# SIM_CARD.net
KiCad netlist of a schematic drawn in Altium Designer
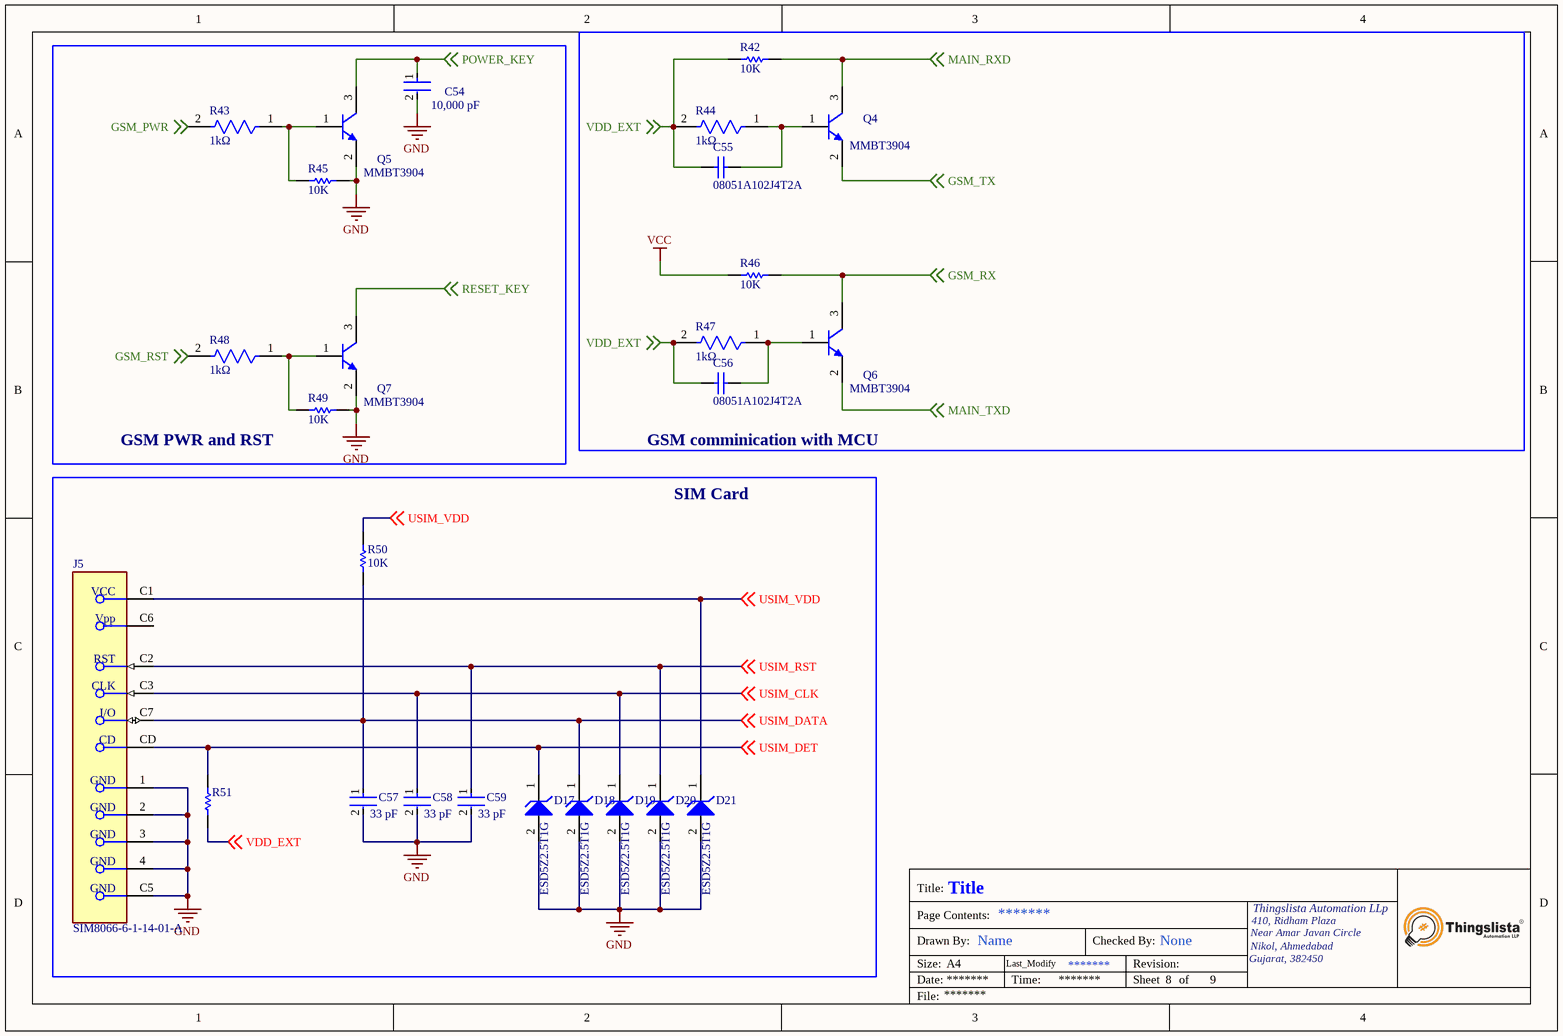
[diagram p0: SIM CARD.SchDoc]

(export (version "E")
  (design (tool "Eeschema 10.0.6"))
  (components
    (comp (ref "C54")
      (value "10,000 pF")
      (footprint "FP-C0805C-DN-MFG")
      (description "CAP CER 10000PF 200V X7R 0805")
      (fields
        (field (name "OCTOPART") "https://octopart.com/c0805c103k2ractu-kemet-9138347")
        (field (name "MANUFACTURER PART NUMBER") "C0805C103K2RACTU")
      )
      (libsource (lib "Altium Content Vault") (part "b4654b650e69147ec39a6b967a45e02"))
    )
    (comp (ref "C55")
      (value "08051A102J4T2A")
      (footprint "CAPC2013X94X50NL20T25")
      (fields (field (name "MANUFACTURER") "AVX Interconnect / Elco"))
      (libsource (lib "Altium Content Vault") (part "CAP"))
    )
    (comp (ref "C56")
      (value "08051A102J4T2A")
      (footprint "CAPC2013X94X50NL20T25")
      (fields (field (name "MANUFACTURER") "AVX Interconnect / Elco"))
      (libsource (lib "Altium Content Vault") (part "CAP"))
    )
    (comp (ref "C57")
      (value "33 pF")
      (footprint "FP-C1206C-EB-MFG")
      (description "CAP CER 33PF 16V NP0 1206")
      (fields (field (name "TOLERANCE") "0.2") (field (name "MANUFACTURER PART NUMBER") "C1206C330M4GACTU"))
      (libsource (lib "Altium Content Vault") (part "b4654b650e69147ec39a6b967a45e02"))
    )
    (comp (ref "C58")
      (value "33 pF")
      (footprint "FP-C1206C-EB-MFG")
      (description "CAP CER 33PF 16V NP0 1206")
      (fields (field (name "TOLERANCE") "0.2") (field (name "MANUFACTURER PART NUMBER") "C1206C330M4GACTU"))
      (libsource (lib "Altium Content Vault") (part "b4654b650e69147ec39a6b967a45e02"))
    )
    (comp (ref "C59")
      (value "33 pF")
      (footprint "FP-C1206C-EB-MFG")
      (description "CAP CER 33PF 16V NP0 1206")
      (fields (field (name "TOLERANCE") "0.2") (field (name "MANUFACTURER PART NUMBER") "C1206C330M4GACTU"))
      (libsource (lib "Altium Content Vault") (part "b4654b650e69147ec39a6b967a45e02"))
    )
    (comp (ref "D17")
      (value "ESD5Z2.5T1G")
      (footprint "ONSC-SOD-523-2-502-01_V")
      (fields (field (name "MANUFACTURER") "On Semiconductor"))
      (libsource (lib "Altium Content Vault") (part "ONSC-K1A2-2"))
    )
    (comp (ref "D18")
      (value "ESD5Z2.5T1G")
      (footprint "ONSC-SOD-523-2-502-01_V")
      (fields (field (name "MANUFACTURER") "On Semiconductor"))
      (libsource (lib "Altium Content Vault") (part "ONSC-K1A2-2"))
    )
    (comp (ref "D19")
      (value "ESD5Z2.5T1G")
      (footprint "ONSC-SOD-523-2-502-01_V")
      (fields (field (name "MANUFACTURER") "On Semiconductor"))
      (libsource (lib "Altium Content Vault") (part "ONSC-K1A2-2"))
    )
    (comp (ref "D20")
      (value "ESD5Z2.5T1G")
      (footprint "ONSC-SOD-523-2-502-01_V")
      (fields (field (name "MANUFACTURER") "On Semiconductor"))
      (libsource (lib "Altium Content Vault") (part "ONSC-K1A2-2"))
    )
    (comp (ref "D21")
      (value "ESD5Z2.5T1G")
      (footprint "ONSC-SOD-523-2-502-01_V")
      (fields (field (name "MANUFACTURER") "On Semiconductor"))
      (libsource (lib "Altium Content Vault") (part "ONSC-K1A2-2"))
    )
    (comp (ref "J5")
      (value "SIM8066-6-1-14-01-A")
      (footprint "FP-SIM8066-6-1-14-01-A-MFG")
      (description "SIM8066-6-1-14-01-A Memory Card Connectors 1.44mm Nano SIM Conn w/Peg and Switch")
      (libsource (lib "Altium Content Vault") (part "1421b091a134f49a34fd3b08e40bfdd"))
    )
    (comp (ref "Q4")
      (value "MMBT3904")
      (footprint "FAIR-SOT23-3_V")
      (description "NPN General Purpose Amplifier, 40 V, 0.2 A, -55 to 150 degC, 3-Pin SOT23, RoHS, Tape and Reel")
      (fields (field (name "TOLERANCE") "30ppm"))
      (libsource (lib "Altium Content Vault") (part "BJT-NPN-BEC-3"))
    )
    (comp (ref "Q5")
      (value "MMBT3904")
      (footprint "FAIR-SOT23-3_V")
      (description "NPN General Purpose Amplifier, 40 V, 0.2 A, -55 to 150 degC, 3-Pin SOT23, RoHS, Tape and Reel")
      (fields (field (name "TOLERANCE") "30ppm"))
      (libsource (lib "Altium Content Vault") (part "BJT-NPN-BEC-3"))
    )
    (comp (ref "Q6")
      (value "MMBT3904")
      (footprint "FAIR-SOT23-3_V")
      (description "NPN General Purpose Amplifier, 40 V, 0.2 A, -55 to 150 degC, 3-Pin SOT23, RoHS, Tape and Reel")
      (fields (field (name "TOLERANCE") "30ppm"))
      (libsource (lib "Altium Content Vault") (part "BJT-NPN-BEC-3"))
    )
    (comp (ref "Q7")
      (value "MMBT3904")
      (footprint "FAIR-SOT23-3_V")
      (description "NPN General Purpose Amplifier, 40 V, 0.2 A, -55 to 150 degC, 3-Pin SOT23, RoHS, Tape and Reel")
      (fields (field (name "TOLERANCE") "30ppm"))
      (libsource (lib "Altium Content Vault") (part "BJT-NPN-BEC-3"))
    )
    (comp (ref "R42")
      (value "10K")
      (footprint "RESC2013X60X35NL10T20")
      (description "Chip Resistor, 10 KOhm, +/- 1%, 0.125 W, -55 to 155 degC, 0805 (2012 Metric), RoHS, Tape and Reel")
      (fields (field (name "MANUFACTURER") "Yageo") (field (name "Comment") "RC0805FR-0710KL"))
      (libsource (lib "Altium Content Vault") (part "RES-2"))
    )
    (comp (ref "R43")
      (value "CRG0805F1K0")
      (footprint "FP-CRG0805-IPC_A")
      (description "CRG0805F1K0 Thick Film Resistors - SMD 1K Ohm 1% 1/8W Res Thick Film 0805")
      (fields (field (name "TOLERANCE") "1%") (field (name "RESISTANCE") "1kΩ"))
      (libsource (lib "Altium Content Vault") (part "1029c3af85768c4190bb7ad29bc67b5"))
    )
    (comp (ref "R44")
      (value "CRG0805F1K0")
      (footprint "FP-CRG0805-IPC_A")
      (description "CRG0805F1K0 Thick Film Resistors - SMD 1K Ohm 1% 1/8W Res Thick Film 0805")
      (fields (field (name "TOLERANCE") "1%") (field (name "RESISTANCE") "1kΩ"))
      (libsource (lib "Altium Content Vault") (part "1029c3af85768c4190bb7ad29bc67b5"))
    )
    (comp (ref "R45")
      (value "10K")
      (footprint "RESC2013X60X35NL10T20")
      (description "Chip Resistor, 10 KOhm, +/- 1%, 0.125 W, -55 to 155 degC, 0805 (2012 Metric), RoHS, Tape and Reel")
      (fields (field (name "MANUFACTURER") "Yageo") (field (name "Comment") "RC0805FR-0710KL"))
      (libsource (lib "Altium Content Vault") (part "RES-2"))
    )
    (comp (ref "R46")
      (value "10K")
      (footprint "RESC2013X60X35NL10T20")
      (description "Chip Resistor, 10 KOhm, +/- 1%, 0.125 W, -55 to 155 degC, 0805 (2012 Metric), RoHS, Tape and Reel")
      (fields (field (name "MANUFACTURER") "Yageo") (field (name "Comment") "RC0805FR-0710KL"))
      (libsource (lib "Altium Content Vault") (part "RES-2"))
    )
    (comp (ref "R47")
      (value "CRG0805F1K0")
      (footprint "FP-CRG0805-IPC_A")
      (description "CRG0805F1K0 Thick Film Resistors - SMD 1K Ohm 1% 1/8W Res Thick Film 0805")
      (fields (field (name "TOLERANCE") "1%") (field (name "RESISTANCE") "1kΩ"))
      (libsource (lib "Altium Content Vault") (part "1029c3af85768c4190bb7ad29bc67b5"))
    )
    (comp (ref "R48")
      (value "CRG0805F1K0")
      (footprint "FP-CRG0805-IPC_A")
      (description "CRG0805F1K0 Thick Film Resistors - SMD 1K Ohm 1% 1/8W Res Thick Film 0805")
      (fields (field (name "TOLERANCE") "1%") (field (name "RESISTANCE") "1kΩ"))
      (libsource (lib "Altium Content Vault") (part "1029c3af85768c4190bb7ad29bc67b5"))
    )
    (comp (ref "R49")
      (value "10K")
      (footprint "RESC2013X60X35NL10T20")
      (description "Chip Resistor, 10 KOhm, +/- 1%, 0.125 W, -55 to 155 degC, 0805 (2012 Metric), RoHS, Tape and Reel")
      (fields (field (name "MANUFACTURER") "Yageo") (field (name "Comment") "RC0805FR-0710KL"))
      (libsource (lib "Altium Content Vault") (part "RES-2"))
    )
    (comp (ref "R50")
      (value "10K")
      (footprint "RESC2013X60X35NL10T20")
      (description "Chip Resistor, 10 KOhm, +/- 1%, 0.125 W, -55 to 155 degC, 0805 (2012 Metric), RoHS, Tape and Reel")
      (fields (field (name "MANUFACTURER") "Yageo") (field (name "Comment") "RC0805FR-0710KL"))
      (libsource (lib "Altium Content Vault") (part "RES-2"))
    )
    (comp (ref "R51")
      (value "CRCW080551K0FKEA")
      (footprint "RESC2013X50X30NL20T20")
      (fields (field (name "MANUFACTURER") "Vishay Dale"))
      (libsource (lib "Altium Content Vault") (part "RES"))
    )
  )
  (nets
    (net (code "1") (name "GND") (class "Default")
      (node (ref "C54") (pin "2") (pinfunction "2_2") (pintype "passive"))
      (node (ref "C57") (pin "2") (pinfunction "2_2") (pintype "passive"))
      (node (ref "C58") (pin "2") (pinfunction "2_2") (pintype "passive"))
      (node (ref "C59") (pin "2") (pinfunction "2_2") (pintype "passive"))
      (node (ref "D17") (pin "2") (pinfunction "A_2") (pintype "passive"))
      (node (ref "D18") (pin "2") (pinfunction "A_2") (pintype "passive"))
      (node (ref "D19") (pin "2") (pinfunction "A_2") (pintype "passive"))
      (node (ref "D20") (pin "2") (pinfunction "A_2") (pintype "passive"))
      (node (ref "D21") (pin "2") (pinfunction "A_2") (pintype "passive"))
      (node (ref "J5") (pin "1") (pinfunction "GND_1") (pintype "power_in"))
      (node (ref "J5") (pin "2") (pinfunction "GND_2") (pintype "power_in"))
      (node (ref "J5") (pin "3") (pinfunction "GND_3") (pintype "power_in"))
      (node (ref "J5") (pin "4") (pinfunction "GND_4") (pintype "power_in"))
      (node (ref "J5") (pin "C5") (pinfunction "GND_C5") (pintype "power_in"))
      (node (ref "Q5") (pin "2") (pinfunction "E_2") (pintype "passive"))
      (node (ref "Q7") (pin "2") (pinfunction "E_2") (pintype "passive"))
      (node (ref "R45") (pin "1") (pinfunction "1_1") (pintype "passive"))
      (node (ref "R49") (pin "1") (pinfunction "1_1") (pintype "passive"))
    )
    (net (code "2") (name "GSM_PWR") (class "Default")
      (node (ref "R43") (pin "2") (pinfunction "2_2") (pintype "passive"))
    )
    (net (code "3") (name "GSM_RST") (class "Default")
      (node (ref "R48") (pin "2") (pinfunction "2_2") (pintype "passive"))
    )
    (net (code "4") (name "GSM_RX") (class "Default")
      (node (ref "Q6") (pin "3") (pinfunction "C_3") (pintype "passive"))
      (node (ref "R46") (pin "1") (pinfunction "1_1") (pintype "passive"))
    )
    (net (code "5") (name "GSM_TX") (class "Default")
      (node (ref "Q4") (pin "2") (pinfunction "E_2") (pintype "passive"))
    )
    (net (code "6") (name "MAIN_RXD") (class "Default")
      (node (ref "Q4") (pin "3") (pinfunction "C_3") (pintype "passive"))
      (node (ref "R42") (pin "1") (pinfunction "1_1") (pintype "passive"))
    )
    (net (code "7") (name "MAIN_TXD") (class "Default")
      (node (ref "Q6") (pin "2") (pinfunction "E_2") (pintype "passive"))
    )
    (net (code "8") (name "Net-(Q4-B)") (class "Default")
      (node (ref "C55") (pin "2") (pinfunction "2_2") (pintype "passive"))
      (node (ref "Q4") (pin "1") (pinfunction "B_1") (pintype "passive"))
      (node (ref "R44") (pin "1") (pinfunction "1_1") (pintype "passive"))
    )
    (net (code "9") (name "Net-(Q5-B)") (class "Default")
      (node (ref "Q5") (pin "1") (pinfunction "B_1") (pintype "passive"))
      (node (ref "R43") (pin "1") (pinfunction "1_1") (pintype "passive"))
      (node (ref "R45") (pin "2") (pinfunction "2_2") (pintype "passive"))
    )
    (net (code "10") (name "Net-(Q6-B)") (class "Default")
      (node (ref "C56") (pin "2") (pinfunction "2_2") (pintype "passive"))
      (node (ref "Q6") (pin "1") (pinfunction "B_1") (pintype "passive"))
      (node (ref "R47") (pin "1") (pinfunction "1_1") (pintype "passive"))
    )
    (net (code "11") (name "Net-(Q7-B)") (class "Default")
      (node (ref "Q7") (pin "1") (pinfunction "B_1") (pintype "passive"))
      (node (ref "R48") (pin "1") (pinfunction "1_1") (pintype "passive"))
      (node (ref "R49") (pin "2") (pinfunction "2_2") (pintype "passive"))
    )
    (net (code "12") (name "POWER_KEY") (class "Default")
      (node (ref "C54") (pin "1") (pinfunction "1_1") (pintype "passive"))
      (node (ref "Q5") (pin "3") (pinfunction "C_3") (pintype "passive"))
    )
    (net (code "13") (name "RESET_KEY") (class "Default")
      (node (ref "Q7") (pin "3") (pinfunction "C_3") (pintype "passive"))
    )
    (net (code "14") (name "USIM_CLK") (class "Default")
      (node (ref "C58") (pin "1") (pinfunction "1_1") (pintype "passive"))
      (node (ref "D19") (pin "1") (pinfunction "K_1") (pintype "passive"))
      (node (ref "J5") (pin "C3") (pinfunction "CLK_C3") (pintype "input"))
    )
    (net (code "15") (name "USIM_DATA") (class "Default")
      (node (ref "C57") (pin "1") (pinfunction "1_1") (pintype "passive"))
      (node (ref "D18") (pin "1") (pinfunction "K_1") (pintype "passive"))
      (node (ref "J5") (pin "C7") (pinfunction "I/O_C7") (pintype "bidirectional"))
      (node (ref "R50") (pin "2") (pinfunction "2_2") (pintype "passive"))
    )
    (net (code "16") (name "USIM_DET") (class "Default")
      (node (ref "D17") (pin "1") (pinfunction "K_1") (pintype "passive"))
      (node (ref "J5") (pin "CD") (pinfunction "CD_CD") (pintype "passive"))
      (node (ref "R51") (pin "2") (pinfunction "2_2") (pintype "passive"))
    )
    (net (code "17") (name "USIM_RST") (class "Default")
      (node (ref "C59") (pin "1") (pinfunction "1_1") (pintype "passive"))
      (node (ref "D20") (pin "1") (pinfunction "K_1") (pintype "passive"))
      (node (ref "J5") (pin "C2") (pinfunction "RST_C2") (pintype "input"))
    )
    (net (code "18") (name "USIM_VDD") (class "Default")
      (node (ref "D21") (pin "1") (pinfunction "K_1") (pintype "passive"))
      (node (ref "J5") (pin "C1") (pinfunction "VCC_C1") (pintype "power_in"))
      (node (ref "R50") (pin "1") (pinfunction "1_1") (pintype "passive"))
    )
    (net (code "19") (name "VCC") (class "Default")
      (node (ref "R46") (pin "2") (pinfunction "2_2") (pintype "passive"))
    )
    (net (code "20") (name "VDD_EXT") (class "Default")
      (node (ref "C55") (pin "1") (pinfunction "1_1") (pintype "passive"))
      (node (ref "C56") (pin "1") (pinfunction "1_1") (pintype "passive"))
      (node (ref "R42") (pin "2") (pinfunction "2_2") (pintype "passive"))
      (node (ref "R44") (pin "2") (pinfunction "2_2") (pintype "passive"))
      (node (ref "R47") (pin "2") (pinfunction "2_2") (pintype "passive"))
      (node (ref "R51") (pin "1") (pinfunction "1_1") (pintype "passive"))
    )
    (net (code "21") (name "unconnected-(J5-Vpp-PadC6)") (class "Default")
      (node (ref "J5") (pin "C6") (pinfunction "Vpp_C6") (pintype "power_in"))
    )
  )
)
